# G792A.net
KiCad netlist of a schematic drawn in EAGLE
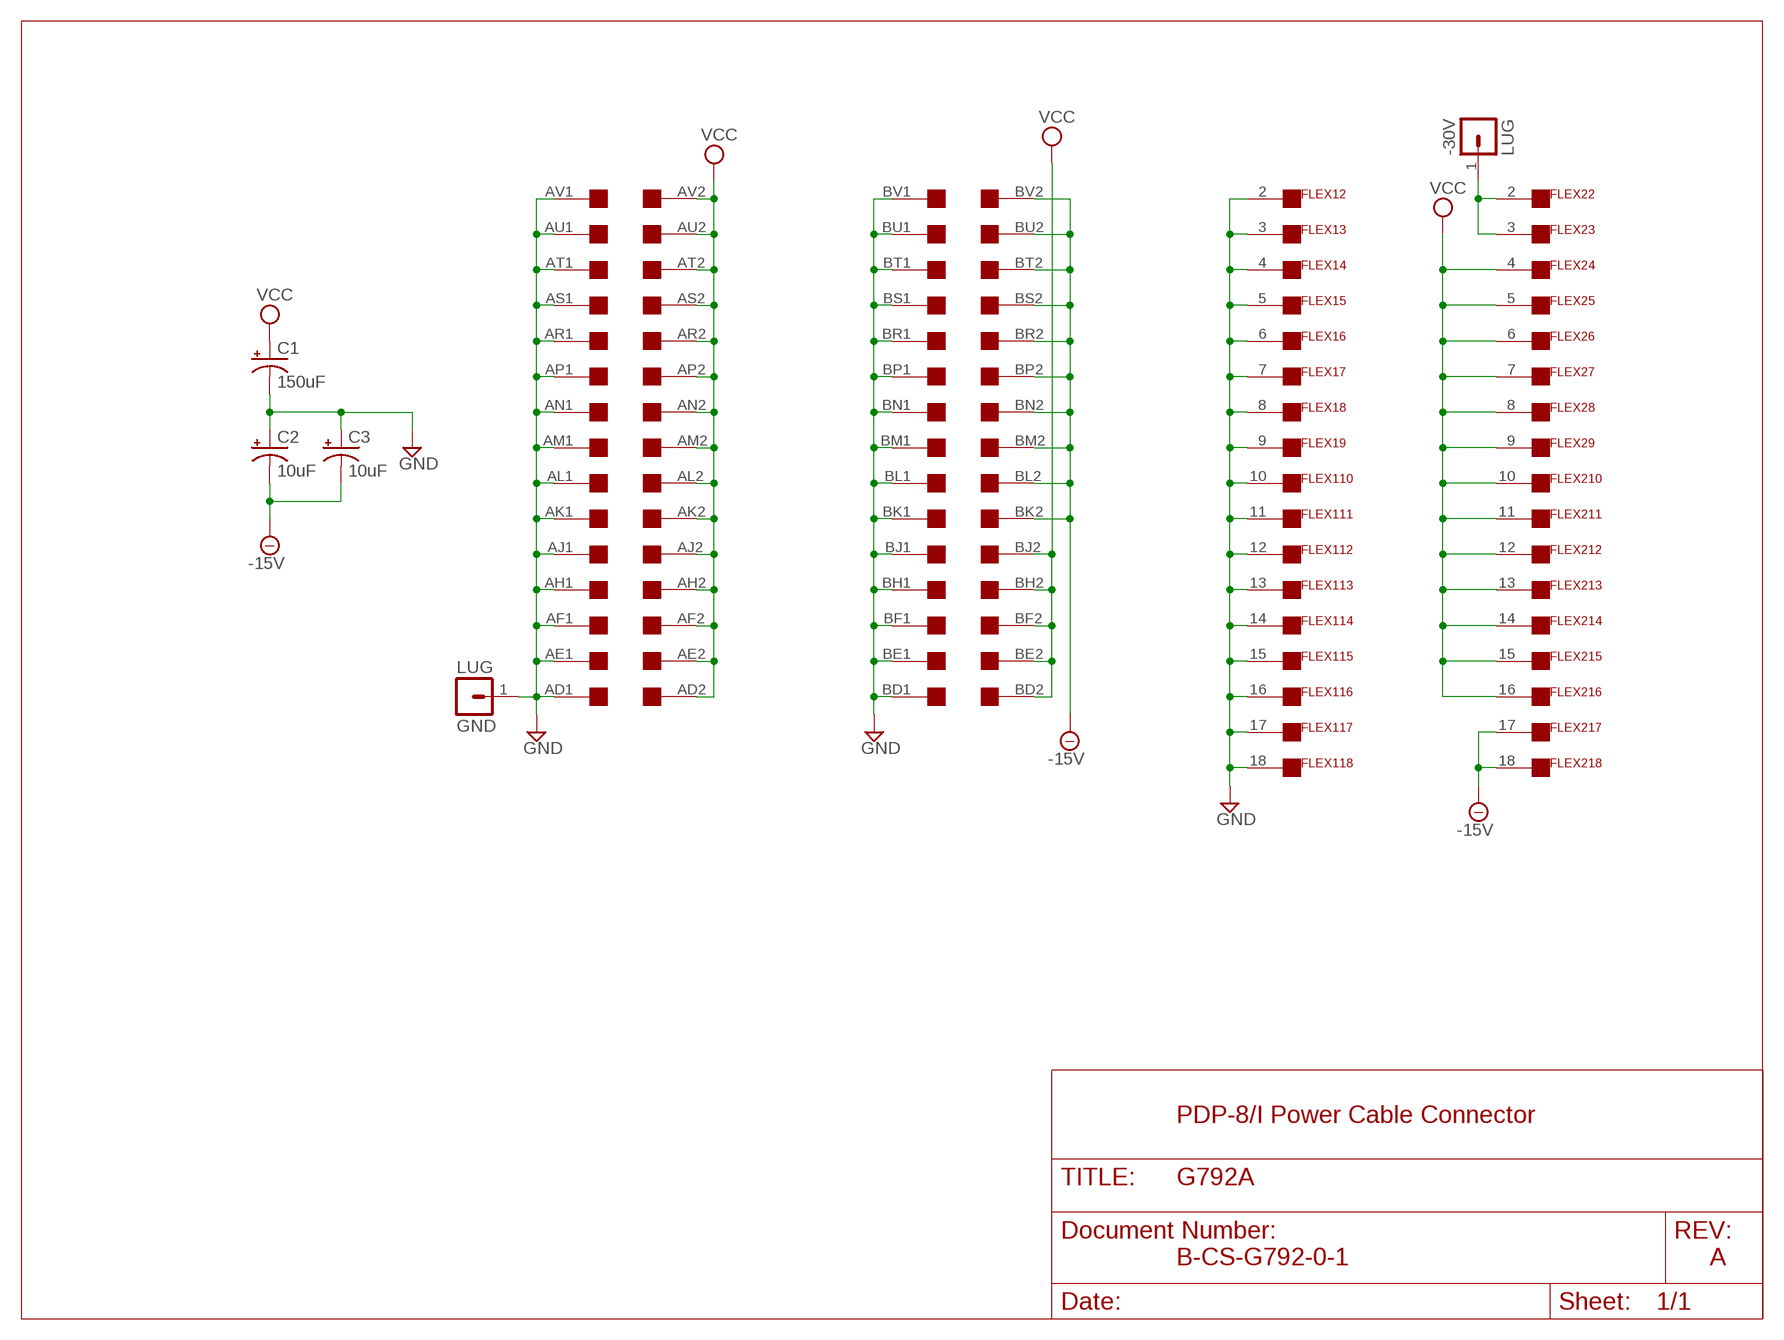
[diagram p0: schematic, sheet 1]

(export (version "E")
  (design (tool "Eeschema 10.0.6"))
  (components
    (comp (ref "-30V")
      (value "LUG")
      (footprint "eagle-import:SPADELUG")
      (libsource (lib "eagle-import") (part "LUG"))
    )
    (comp (ref "C1")
      (value "150uF")
      (footprint "eagle-import:E25-9")
      (libsource (lib "eagle-import") (part "CPOL-USE25-9AXIAL"))
    )
    (comp (ref "C2")
      (value "10uF")
      (footprint "eagle-import:E25-9")
      (libsource (lib "eagle-import") (part "CPOL-USE25-9AXIAL"))
    )
    (comp (ref "C3")
      (value "10uF")
      (footprint "eagle-import:E25-9")
      (libsource (lib "eagle-import") (part "CPOL-USE25-9AXIAL"))
    )
    (comp (ref "FLEX1")
      (value "FLEX19W")
      (footprint "eagle-import:FLEX19W")
      (libsource (lib "eagle-import") (part "FLEX19W"))
    )
    (comp (ref "FLEX2")
      (value "FLEX19W")
      (footprint "eagle-import:FLEX19W")
      (libsource (lib "eagle-import") (part "FLEX19W"))
    )
    (comp (ref "GND")
      (value "LUG")
      (footprint "eagle-import:SPADELUG")
      (libsource (lib "eagle-import") (part "LUG"))
    )
    (comp (ref "U$2")
      (value "DOUBLE")
      (footprint "eagle-import:EDGE-CON4")
      (libsource (lib "eagle-import") (part "DOUBLE"))
    )
  )
  (nets
    (net (code "1") (name "-15V") (class "Default")
      (node (ref "C2") (pin "-") (pinfunction "-_-") (pintype "passive"))
      (node (ref "C3") (pin "-") (pinfunction "-_-") (pintype "passive"))
      (node (ref "FLEX2") (pin "17") (pinfunction "1_17") (pintype "passive"))
      (node (ref "FLEX2") (pin "18") (pinfunction "1_18") (pintype "passive"))
      (node (ref "U$2") (pin "BK2") (pinfunction "1_BK2") (pintype "bidirectional"))
      (node (ref "U$2") (pin "BL2") (pinfunction "1_BL2") (pintype "bidirectional"))
      (node (ref "U$2") (pin "BM2") (pinfunction "1_BM2") (pintype "bidirectional"))
      (node (ref "U$2") (pin "BN2") (pinfunction "1_BN2") (pintype "bidirectional"))
      (node (ref "U$2") (pin "BP2") (pinfunction "1_BP2") (pintype "bidirectional"))
      (node (ref "U$2") (pin "BR2") (pinfunction "1_BR2") (pintype "bidirectional"))
      (node (ref "U$2") (pin "BS2") (pinfunction "1_BS2") (pintype "bidirectional"))
      (node (ref "U$2") (pin "BT2") (pinfunction "1_BT2") (pintype "bidirectional"))
      (node (ref "U$2") (pin "BU2") (pinfunction "1_BU2") (pintype "bidirectional"))
      (node (ref "U$2") (pin "BV2") (pinfunction "1_BV2") (pintype "bidirectional"))
    )
    (net (code "2") (name "GND") (class "Default")
      (node (ref "C1") (pin "-") (pinfunction "-_-") (pintype "passive"))
      (node (ref "C2") (pin "+") (pinfunction "+_+") (pintype "passive"))
      (node (ref "C3") (pin "+") (pinfunction "+_+") (pintype "passive"))
      (node (ref "FLEX1") (pin "10") (pinfunction "1_10") (pintype "passive"))
      (node (ref "FLEX1") (pin "11") (pinfunction "1_11") (pintype "passive"))
      (node (ref "FLEX1") (pin "12") (pinfunction "1_12") (pintype "passive"))
      (node (ref "FLEX1") (pin "13") (pinfunction "1_13") (pintype "passive"))
      (node (ref "FLEX1") (pin "14") (pinfunction "1_14") (pintype "passive"))
      (node (ref "FLEX1") (pin "15") (pinfunction "1_15") (pintype "passive"))
      (node (ref "FLEX1") (pin "16") (pinfunction "1_16") (pintype "passive"))
      (node (ref "FLEX1") (pin "17") (pinfunction "1_17") (pintype "passive"))
      (node (ref "FLEX1") (pin "18") (pinfunction "1_18") (pintype "passive"))
      (node (ref "FLEX1") (pin "2") (pinfunction "1_2") (pintype "passive"))
      (node (ref "FLEX1") (pin "3") (pinfunction "1_3") (pintype "passive"))
      (node (ref "FLEX1") (pin "4") (pinfunction "1_4") (pintype "passive"))
      (node (ref "FLEX1") (pin "5") (pinfunction "1_5") (pintype "passive"))
      (node (ref "FLEX1") (pin "6") (pinfunction "1_6") (pintype "passive"))
      (node (ref "FLEX1") (pin "7") (pinfunction "1_7") (pintype "passive"))
      (node (ref "FLEX1") (pin "8") (pinfunction "1_8") (pintype "passive"))
      (node (ref "FLEX1") (pin "9") (pinfunction "1_9") (pintype "passive"))
      (node (ref "GND") (pin "1") (pinfunction "1_1") (pintype "passive"))
      (node (ref "U$2") (pin "AD1") (pinfunction "1_AD1") (pintype "bidirectional"))
      (node (ref "U$2") (pin "AE1") (pinfunction "1_AE1") (pintype "bidirectional"))
      (node (ref "U$2") (pin "AF1") (pinfunction "1_AF1") (pintype "bidirectional"))
      (node (ref "U$2") (pin "AH1") (pinfunction "1_AH1") (pintype "bidirectional"))
      (node (ref "U$2") (pin "AJ1") (pinfunction "1_AJ1") (pintype "bidirectional"))
      (node (ref "U$2") (pin "AK1") (pinfunction "1_AK1") (pintype "bidirectional"))
      (node (ref "U$2") (pin "AL1") (pinfunction "1_AL1") (pintype "bidirectional"))
      (node (ref "U$2") (pin "AM1") (pinfunction "1_AM1") (pintype "bidirectional"))
      (node (ref "U$2") (pin "AN1") (pinfunction "1_AN1") (pintype "bidirectional"))
      (node (ref "U$2") (pin "AP1") (pinfunction "1_AP1") (pintype "bidirectional"))
      (node (ref "U$2") (pin "AR1") (pinfunction "1_AR1") (pintype "bidirectional"))
      (node (ref "U$2") (pin "AS1") (pinfunction "1_AS1") (pintype "bidirectional"))
      (node (ref "U$2") (pin "AT1") (pinfunction "1_AT1") (pintype "bidirectional"))
      (node (ref "U$2") (pin "AU1") (pinfunction "1_AU1") (pintype "bidirectional"))
      (node (ref "U$2") (pin "AV1") (pinfunction "1_AV1") (pintype "bidirectional"))
      (node (ref "U$2") (pin "BD1") (pinfunction "1_BD1") (pintype "bidirectional"))
      (node (ref "U$2") (pin "BE1") (pinfunction "1_BE1") (pintype "bidirectional"))
      (node (ref "U$2") (pin "BF1") (pinfunction "1_BF1") (pintype "bidirectional"))
      (node (ref "U$2") (pin "BH1") (pinfunction "1_BH1") (pintype "bidirectional"))
      (node (ref "U$2") (pin "BJ1") (pinfunction "1_BJ1") (pintype "bidirectional"))
      (node (ref "U$2") (pin "BK1") (pinfunction "1_BK1") (pintype "bidirectional"))
      (node (ref "U$2") (pin "BL1") (pinfunction "1_BL1") (pintype "bidirectional"))
      (node (ref "U$2") (pin "BM1") (pinfunction "1_BM1") (pintype "bidirectional"))
      (node (ref "U$2") (pin "BN1") (pinfunction "1_BN1") (pintype "bidirectional"))
      (node (ref "U$2") (pin "BP1") (pinfunction "1_BP1") (pintype "bidirectional"))
      (node (ref "U$2") (pin "BR1") (pinfunction "1_BR1") (pintype "bidirectional"))
      (node (ref "U$2") (pin "BS1") (pinfunction "1_BS1") (pintype "bidirectional"))
      (node (ref "U$2") (pin "BT1") (pinfunction "1_BT1") (pintype "bidirectional"))
      (node (ref "U$2") (pin "BU1") (pinfunction "1_BU1") (pintype "bidirectional"))
      (node (ref "U$2") (pin "BV1") (pinfunction "1_BV1") (pintype "bidirectional"))
    )
    (net (code "3") (name "Net-(FLEX2L-1)") (class "Default")
      (node (ref "-30V") (pin "1") (pinfunction "1_1") (pintype "passive"))
      (node (ref "FLEX2") (pin "2") (pinfunction "1_2") (pintype "passive"))
      (node (ref "FLEX2") (pin "3") (pinfunction "1_3") (pintype "passive"))
    )
    (net (code "4") (name "VCC") (class "Default")
      (node (ref "C1") (pin "+") (pinfunction "+_+") (pintype "passive"))
      (node (ref "FLEX2") (pin "10") (pinfunction "1_10") (pintype "passive"))
      (node (ref "FLEX2") (pin "11") (pinfunction "1_11") (pintype "passive"))
      (node (ref "FLEX2") (pin "12") (pinfunction "1_12") (pintype "passive"))
      (node (ref "FLEX2") (pin "13") (pinfunction "1_13") (pintype "passive"))
      (node (ref "FLEX2") (pin "14") (pinfunction "1_14") (pintype "passive"))
      (node (ref "FLEX2") (pin "15") (pinfunction "1_15") (pintype "passive"))
      (node (ref "FLEX2") (pin "16") (pinfunction "1_16") (pintype "passive"))
      (node (ref "FLEX2") (pin "4") (pinfunction "1_4") (pintype "passive"))
      (node (ref "FLEX2") (pin "5") (pinfunction "1_5") (pintype "passive"))
      (node (ref "FLEX2") (pin "6") (pinfunction "1_6") (pintype "passive"))
      (node (ref "FLEX2") (pin "7") (pinfunction "1_7") (pintype "passive"))
      (node (ref "FLEX2") (pin "8") (pinfunction "1_8") (pintype "passive"))
      (node (ref "FLEX2") (pin "9") (pinfunction "1_9") (pintype "passive"))
      (node (ref "U$2") (pin "AD2") (pinfunction "1_AD2") (pintype "bidirectional"))
      (node (ref "U$2") (pin "AE2") (pinfunction "1_AE2") (pintype "bidirectional"))
      (node (ref "U$2") (pin "AF2") (pinfunction "1_AF2") (pintype "bidirectional"))
      (node (ref "U$2") (pin "AH2") (pinfunction "1_AH2") (pintype "bidirectional"))
      (node (ref "U$2") (pin "AJ2") (pinfunction "1_AJ2") (pintype "bidirectional"))
      (node (ref "U$2") (pin "AK2") (pinfunction "1_AK2") (pintype "bidirectional"))
      (node (ref "U$2") (pin "AL2") (pinfunction "1_AL2") (pintype "bidirectional"))
      (node (ref "U$2") (pin "AM2") (pinfunction "1_AM2") (pintype "bidirectional"))
      (node (ref "U$2") (pin "AN2") (pinfunction "1_AN2") (pintype "bidirectional"))
      (node (ref "U$2") (pin "AP2") (pinfunction "1_AP2") (pintype "bidirectional"))
      (node (ref "U$2") (pin "AR2") (pinfunction "1_AR2") (pintype "bidirectional"))
      (node (ref "U$2") (pin "AS2") (pinfunction "1_AS2") (pintype "bidirectional"))
      (node (ref "U$2") (pin "AT2") (pinfunction "1_AT2") (pintype "bidirectional"))
      (node (ref "U$2") (pin "AU2") (pinfunction "1_AU2") (pintype "bidirectional"))
      (node (ref "U$2") (pin "AV2") (pinfunction "1_AV2") (pintype "bidirectional"))
      (node (ref "U$2") (pin "BD2") (pinfunction "1_BD2") (pintype "bidirectional"))
      (node (ref "U$2") (pin "BE2") (pinfunction "1_BE2") (pintype "bidirectional"))
      (node (ref "U$2") (pin "BF2") (pinfunction "1_BF2") (pintype "bidirectional"))
      (node (ref "U$2") (pin "BH2") (pinfunction "1_BH2") (pintype "bidirectional"))
      (node (ref "U$2") (pin "BJ2") (pinfunction "1_BJ2") (pintype "bidirectional"))
    )
  )
)
